# PowerConversionBoard.net
KiCad netlist of a schematic drawn in EAGLE
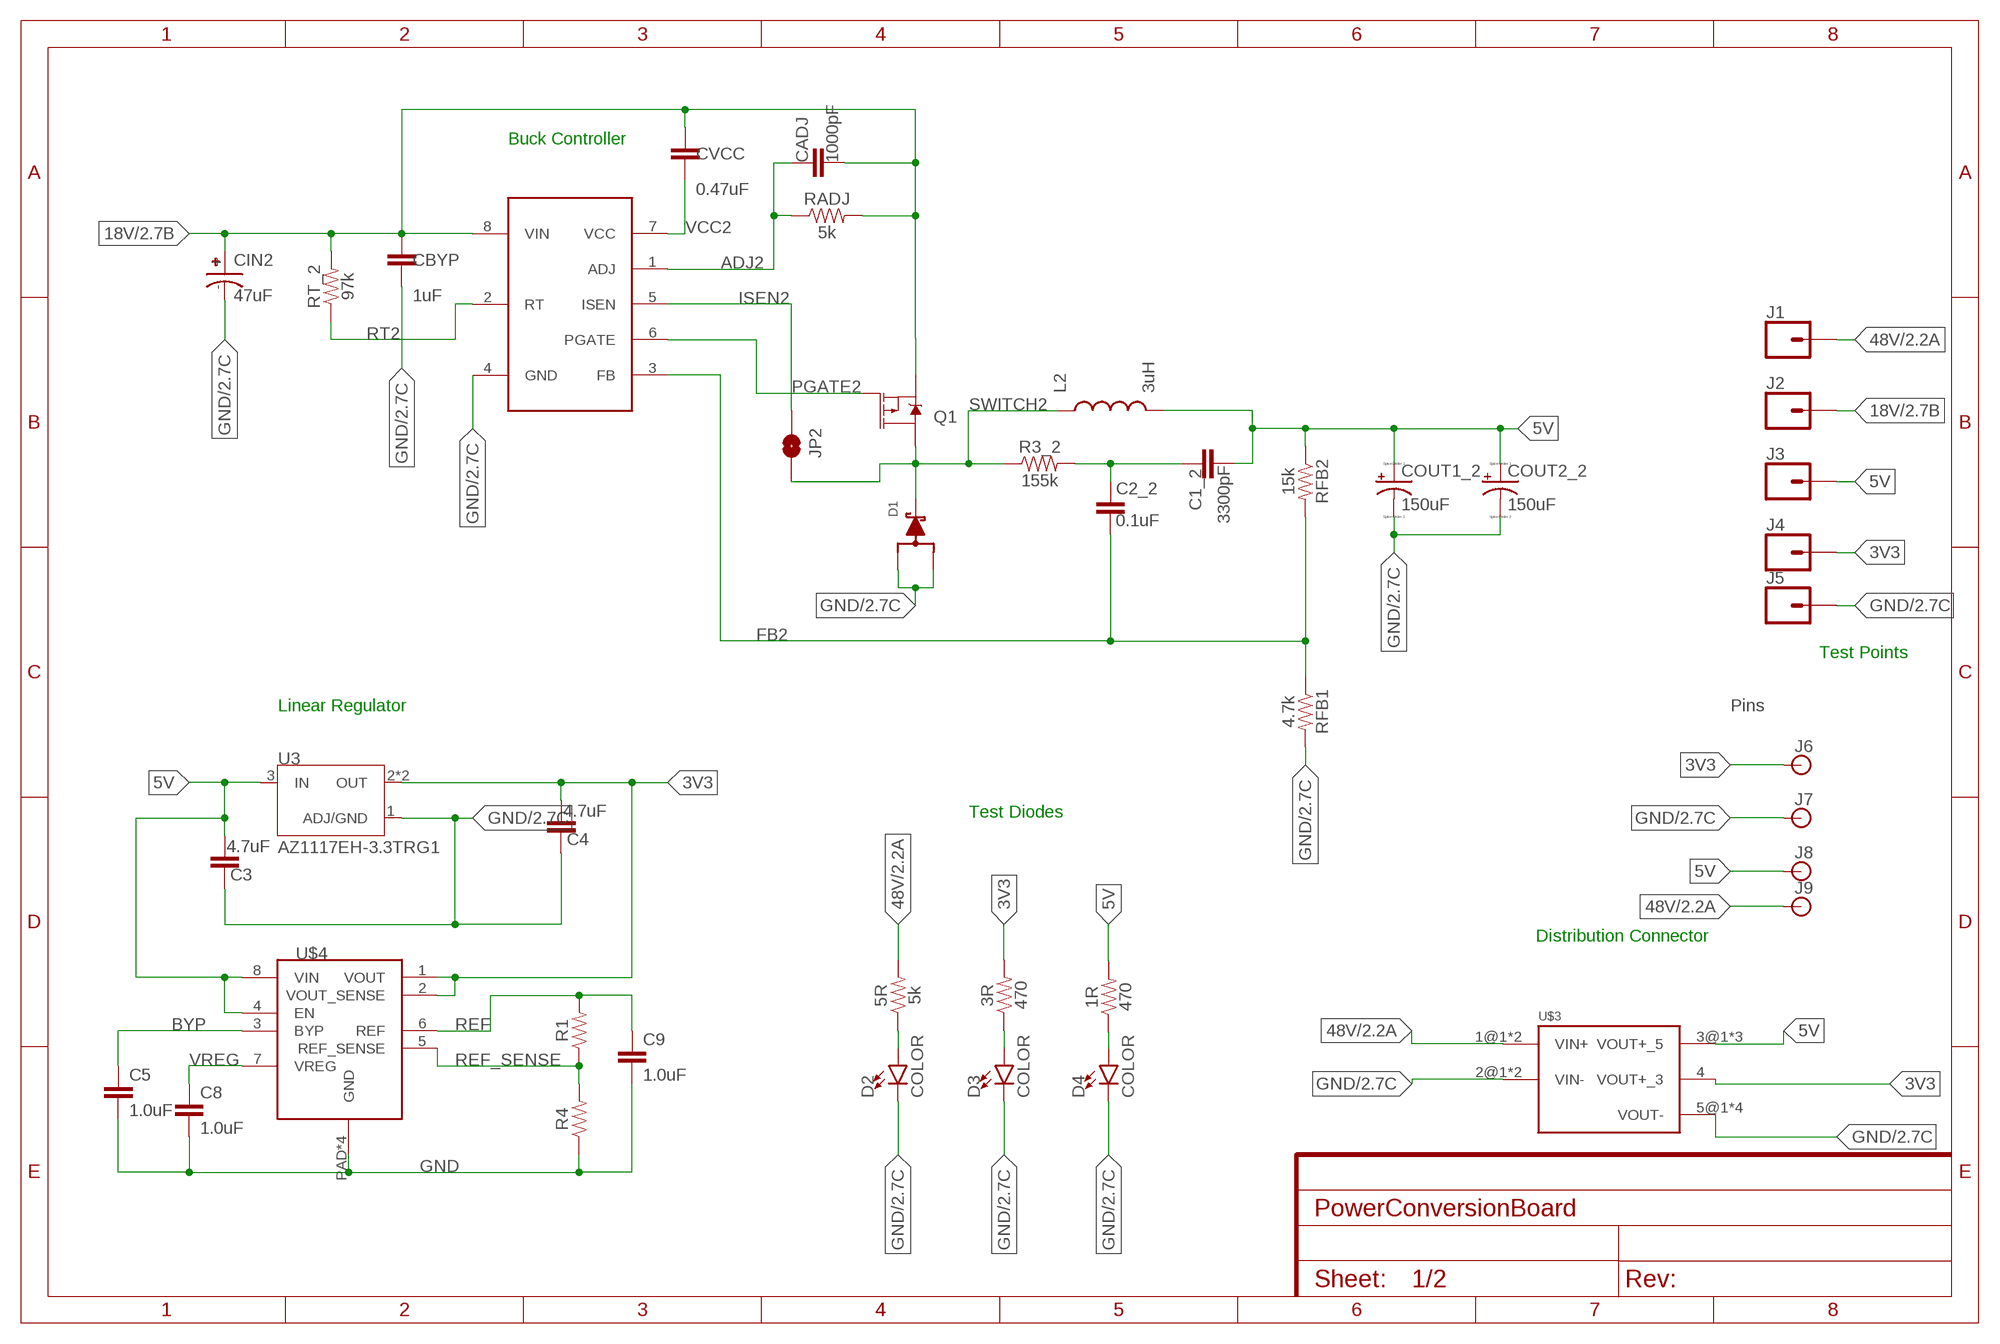
[diagram p0: schematic, sheet 1]
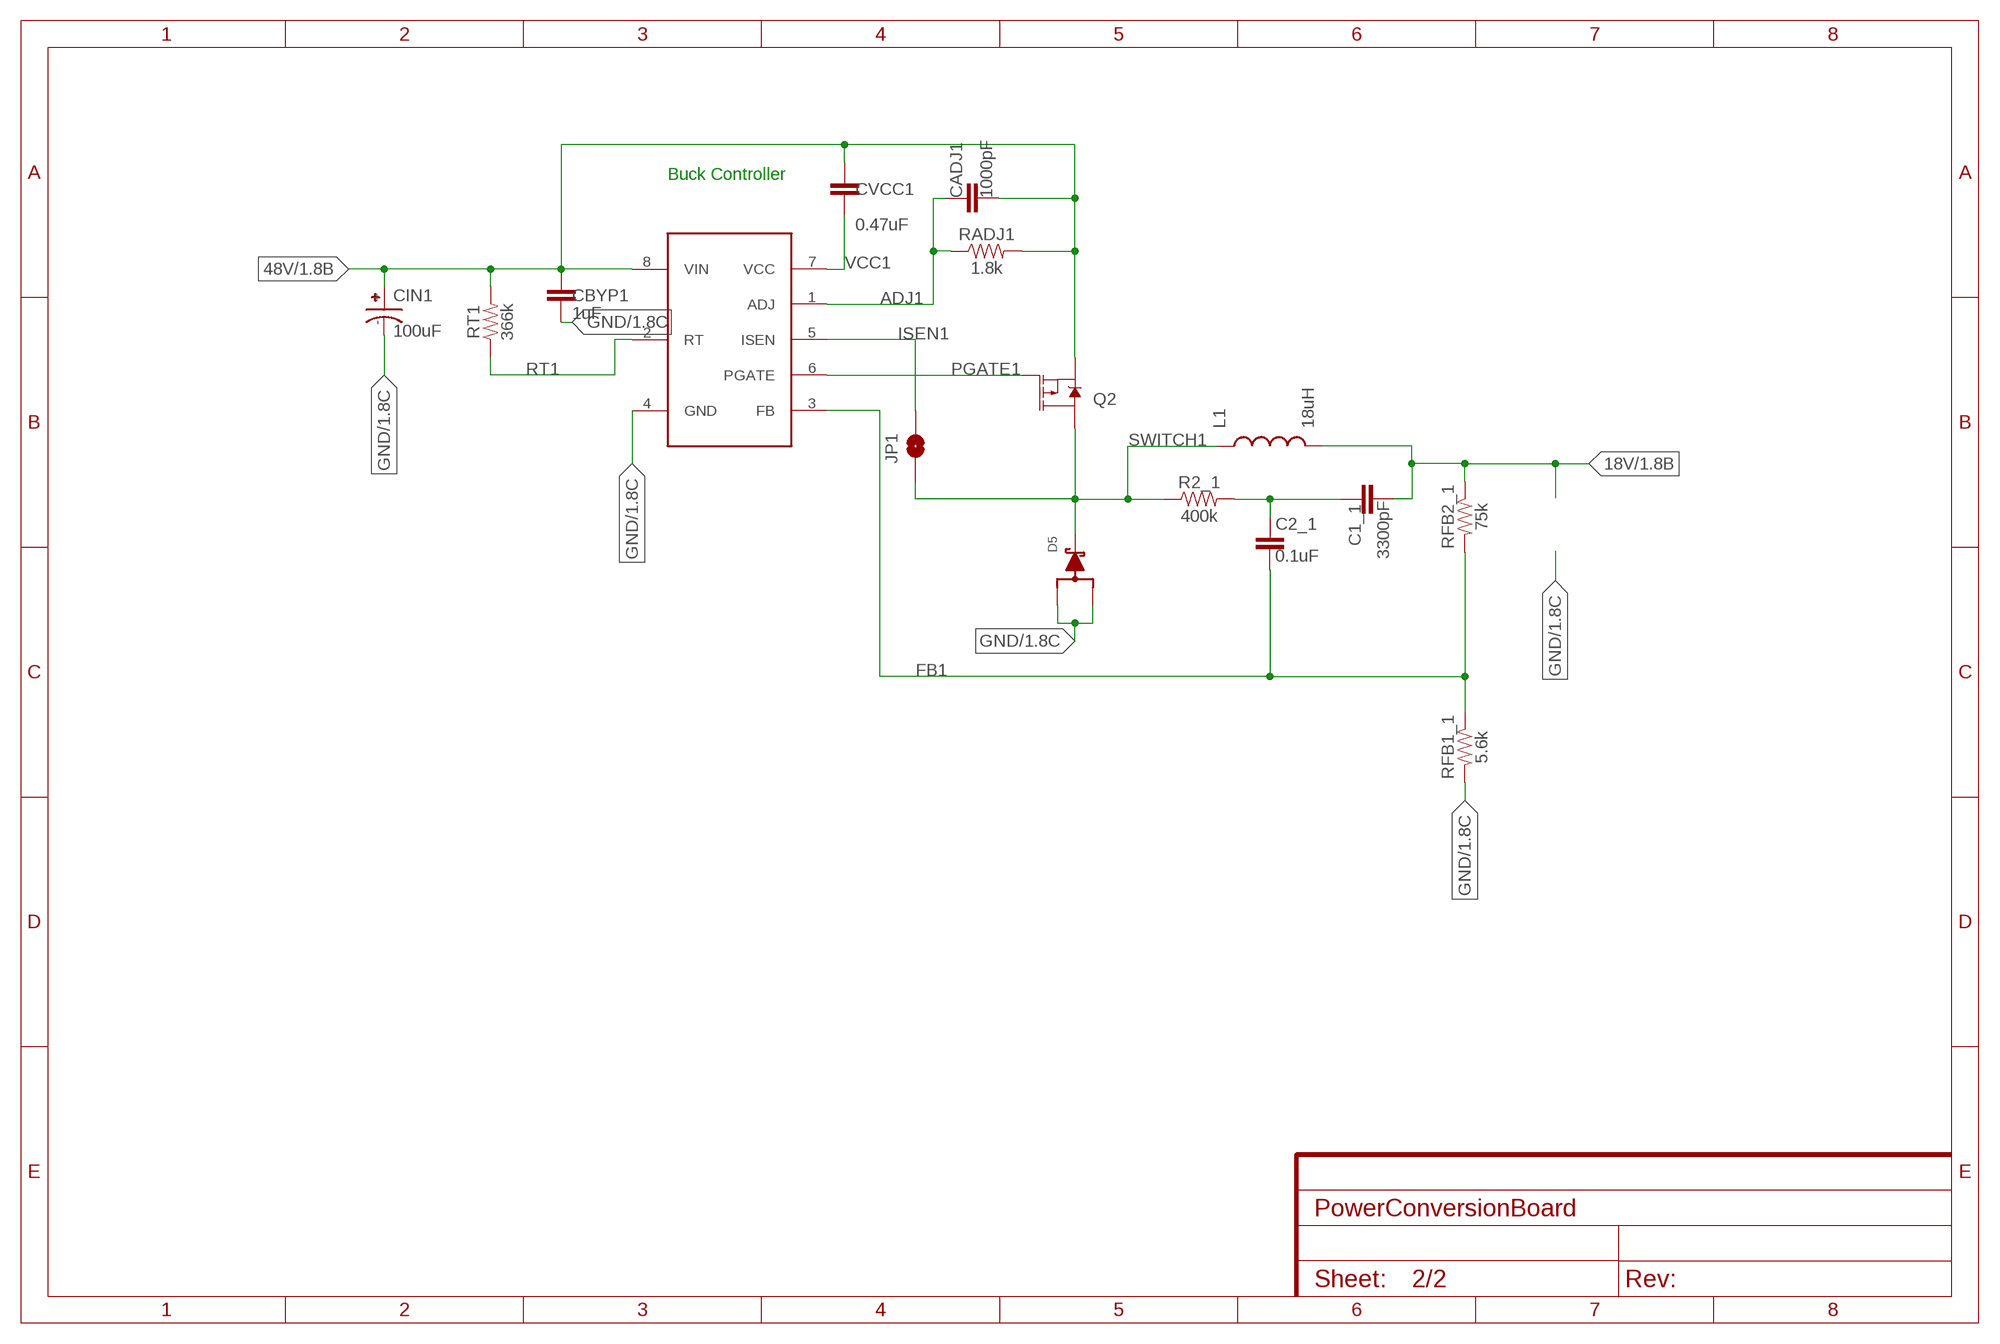
[diagram p1: schematic, sheet 2]

(export (version "E")
  (design (tool "Eeschema 10.0.6"))
  (components
    (comp (ref "1R")
      (value "470")
      (footprint "eagle-import:0603")
      (libsource (lib "eagle-import") (part "470OHM-0603-1/10W-1%"))
    )
    (comp (ref "3R")
      (value "470")
      (footprint "eagle-import:0603")
      (libsource (lib "eagle-import") (part "470OHM-0603-1/10W-1%"))
    )
    (comp (ref "5R")
      (value "5k")
      (footprint "eagle-import:0603")
      (libsource (lib "eagle-import") (part "470OHM-0603-1/10W-1%"))
    )
    (comp (ref "C1_2")
      (value "3300pF")
      (footprint "eagle-import:0603")
      (libsource (lib "eagle-import") (part "12PF-0603-50V-5%"))
    )
    (comp (ref "C2_2")
      (value "0.1uF")
      (footprint "eagle-import:0603")
      (libsource (lib "eagle-import") (part "12PF-0603-50V-5%"))
    )
    (comp (ref "C3")
      (value "4.7uF")
      (footprint "eagle-import:0603")
      (libsource (lib "eagle-import") (part "12PF-0603-50V-5%"))
    )
    (comp (ref "C4")
      (value "4.7uF")
      (footprint "eagle-import:0603")
      (libsource (lib "eagle-import") (part "12PF-0603-50V-5%"))
    )
    (comp (ref "C5")
      (value "1.0uF")
      (footprint "eagle-import:0603")
      (libsource (lib "eagle-import") (part "1.0UF-0603-16V-10%"))
    )
    (comp (ref "C8")
      (value "1.0uF")
      (footprint "eagle-import:0603")
      (libsource (lib "eagle-import") (part "1.0UF-0603-16V-10%"))
    )
    (comp (ref "C9")
      (value "1.0uF")
      (footprint "eagle-import:0603")
      (libsource (lib "eagle-import") (part "1.0UF-0603-16V-10%"))
    )
    (comp (ref "CADJ")
      (value "1000pF")
      (footprint "eagle-import:0603")
      (libsource (lib "eagle-import") (part "5.6PF-0603-50V-5%"))
    )
    (comp (ref "CBYP")
      (value "1uF")
      (footprint "eagle-import:0603")
      (libsource (lib "eagle-import") (part "3.3NF-0603-100V-10%"))
    )
    (comp (ref "CIN2")
      (value "47uF")
      (footprint "eagle-import:CAPAE1030X1050N")
      (fields
        (field (name "ARROW_PART_NUMBER") "UCM1H331MNL1GS")
        (field (name "MOUSER_PART_NUMBER") "647-UCM1H331MNL1GS")
      )
      (libsource (lib "eagle-import") (part "UCM1H331MNL1GS"))
    )
    (comp (ref "COUT1_2")
      (value "150uF")
      (footprint "eagle-import:CTAN(7.30_4.30MM)")
      (libsource (lib "eagle-import") (part "C-TANTALUM(10UF_150UF)"))
    )
    (comp (ref "COUT2_2")
      (value "150uF")
      (footprint "eagle-import:CTAN(7.30_4.30MM)")
      (libsource (lib "eagle-import") (part "C-TANTALUM(10UF_150UF)"))
    )
    (comp (ref "CVCC")
      (value "0.47uF")
      (footprint "eagle-import:0603")
      (libsource (lib "eagle-import") (part "5.6PF-0603-50V-5%"))
    )
    (comp (ref "D1")
      (value "SWITCHMODE_SCHOTTKY")
      (footprint "eagle-import:DPAK-3")
      (libsource (lib "eagle-import") (part "SWITCHMODE_SCHOTTKY"))
    )
    (comp (ref "D2")
      (value "COLOR")
      (footprint "eagle-import:0805")
      (libsource (lib "eagle-import") (part "LED-0805"))
    )
    (comp (ref "D3")
      (value "COLOR")
      (footprint "eagle-import:0805")
      (libsource (lib "eagle-import") (part "LED-0805"))
    )
    (comp (ref "D4")
      (value "COLOR")
      (footprint "eagle-import:0805")
      (libsource (lib "eagle-import") (part "LED-0805"))
    )
    (comp (ref "J1")
      (value "CONN_01")
      (footprint "eagle-import:1X01")
      (libsource (lib "eagle-import") (part "CONN_01"))
    )
    (comp (ref "J2")
      (value "CONN_01")
      (footprint "eagle-import:1X01")
      (libsource (lib "eagle-import") (part "CONN_01"))
    )
    (comp (ref "J3")
      (value "CONN_01")
      (footprint "eagle-import:1X01")
      (libsource (lib "eagle-import") (part "CONN_01"))
    )
    (comp (ref "J4")
      (value "CONN_01")
      (footprint "eagle-import:1X01")
      (libsource (lib "eagle-import") (part "CONN_01"))
    )
    (comp (ref "J5")
      (value "CONN_01")
      (footprint "eagle-import:1X01")
      (libsource (lib "eagle-import") (part "CONN_01"))
    )
    (comp (ref "J6")
      (value "BANANA_PTH")
      (footprint "eagle-import:BANANA_CONN_NO_THERM")
      (libsource (lib "eagle-import") (part "BANANA_PTH"))
    )
    (comp (ref "J7")
      (value "BANANA_PTH")
      (footprint "eagle-import:BANANA_CONN_NO_THERM")
      (libsource (lib "eagle-import") (part "BANANA_PTH"))
    )
    (comp (ref "J8")
      (value "BANANA_PTH")
      (footprint "eagle-import:BANANA_CONN_NO_THERM")
      (libsource (lib "eagle-import") (part "BANANA_PTH"))
    )
    (comp (ref "J9")
      (value "BANANA_PTH")
      (footprint "eagle-import:BANANA_CONN_NO_THERM")
      (libsource (lib "eagle-import") (part "BANANA_PTH"))
    )
    (comp (ref "JP2")
      (value "JUMPER-SMT_2_NO_SILK")
      (footprint "eagle-import:SMT-JUMPER_2_NO_SILK")
      (libsource (lib "eagle-import") (part "JUMPER-SMT_2_NO_SILK"))
    )
    (comp (ref "L2")
      (value "3uH")
      (footprint "eagle-import:HCMA1305")
      (libsource (lib "eagle-import") (part "HCMA1305"))
    )
    (comp (ref "Q1")
      (value "MOSFET_PCH-NDS8434")
      (footprint "eagle-import:SO08")
      (libsource (lib "eagle-import") (part "MOSFET_PCH-NDS8434"))
    )
    (comp (ref "R1")
      (value "RESISTOR0603")
      (footprint "eagle-import:0603")
      (libsource (lib "eagle-import") (part "RESISTOR0603"))
    )
    (comp (ref "R3_2")
      (value "155k")
      (footprint "eagle-import:0603")
      (libsource (lib "eagle-import") (part "RESISTOR0603"))
    )
    (comp (ref "R4")
      (value "RESISTOR0603")
      (footprint "eagle-import:0603")
      (libsource (lib "eagle-import") (part "RESISTOR0603"))
    )
    (comp (ref "RADJ")
      (value "5k")
      (footprint "eagle-import:0603")
      (libsource (lib "eagle-import") (part "RESISTOR0603"))
    )
    (comp (ref "RFB1")
      (value "4.7k")
      (footprint "eagle-import:0603")
      (libsource (lib "eagle-import") (part "RESISTOR0603"))
    )
    (comp (ref "RFB2")
      (value "15k")
      (footprint "eagle-import:0603")
      (libsource (lib "eagle-import") (part "RESISTOR0603"))
    )
    (comp (ref "RT_2")
      (value "97k")
      (footprint "eagle-import:0603")
      (libsource (lib "eagle-import") (part "82OHM-0603-1/10W-1%"))
    )
    (comp (ref "U$1")
      (value "LM5085")
      (footprint "eagle-import:LM5085")
      (libsource (lib "eagle-import") (part "LM5085"))
    )
    (comp (ref "U$3")
      (value "CON2DIST")
      (footprint "eagle-import:CON2DIST")
      (libsource (lib "eagle-import") (part "CON2DIST"))
    )
    (comp (ref "U$4")
      (value "ADP7159ARDZ-04-R7")
      (footprint "eagle-import:8-SOIC-EP")
      (libsource (lib "eagle-import") (part "ADP7159ARDZ-04-R7"))
    )
    (comp (ref "U3")
      (value "AZ1117EH-3.3TRG1")
      (footprint "eagle-import:SOT230P700X180-4N")
      (fields (field (name "MF") "Diodes Inc."))
      (libsource (lib "eagle-import") (part "AZ1117EH-3.3TRG1"))
    )
    (comp (ref "C1_1")
      (value "3300pF")
      (footprint "eagle-import:0603")
      (libsource (lib "eagle-import") (part "12PF-0603-50V-5%"))
    )
    (comp (ref "C2_1")
      (value "0.1uF")
      (footprint "eagle-import:0603")
      (libsource (lib "eagle-import") (part "12PF-0603-50V-5%"))
    )
    (comp (ref "CADJ1")
      (value "1000pF")
      (footprint "eagle-import:0603")
      (libsource (lib "eagle-import") (part "5.6PF-0603-50V-5%"))
    )
    (comp (ref "CBYP1")
      (value "1uF")
      (footprint "eagle-import:0603")
      (libsource (lib "eagle-import") (part "3.3NF-0603-100V-10%"))
    )
    (comp (ref "CIN1")
      (value "100uF")
      (footprint "eagle-import:CAPAE1030X1050N")
      (fields
        (field (name "ARROW_PART_NUMBER") "UCM1H331MNL1GS")
        (field (name "MOUSER_PART_NUMBER") "647-UCM1H331MNL1GS")
      )
      (libsource (lib "eagle-import") (part "UCM1H331MNL1GS"))
    )
    (comp (ref "CVCC1")
      (value "0.47uF")
      (footprint "eagle-import:0603")
      (libsource (lib "eagle-import") (part "5.6PF-0603-50V-5%"))
    )
    (comp (ref "D5")
      (value "SWITCHMODE_SCHOTTKY")
      (footprint "eagle-import:DPAK-3")
      (libsource (lib "eagle-import") (part "SWITCHMODE_SCHOTTKY"))
    )
    (comp (ref "JP1")
      (value "JUMPER-SMT_2_NO_SILK")
      (footprint "eagle-import:SMT-JUMPER_2_NO_SILK")
      (libsource (lib "eagle-import") (part "JUMPER-SMT_2_NO_SILK"))
    )
    (comp (ref "L1")
      (value "18uH")
      (footprint "eagle-import:HCMA1305")
      (libsource (lib "eagle-import") (part "HCMA1305"))
    )
    (comp (ref "Q2")
      (value "MOSFET_PCH-NDS8434")
      (footprint "eagle-import:SO08")
      (libsource (lib "eagle-import") (part "MOSFET_PCH-NDS8434"))
    )
    (comp (ref "R2_1")
      (value "400k")
      (footprint "eagle-import:0603")
      (libsource (lib "eagle-import") (part "RESISTOR0603"))
    )
    (comp (ref "RADJ1")
      (value "1.8k")
      (footprint "eagle-import:0603")
      (libsource (lib "eagle-import") (part "RESISTOR0603"))
    )
    (comp (ref "RFB1_1")
      (value "5.6k")
      (footprint "eagle-import:0603")
      (libsource (lib "eagle-import") (part "RESISTOR0603"))
    )
    (comp (ref "RFB2_1")
      (value "75k")
      (footprint "eagle-import:0603")
      (libsource (lib "eagle-import") (part "RESISTOR0603"))
    )
    (comp (ref "RT1")
      (value "366k")
      (footprint "eagle-import:0603")
      (libsource (lib "eagle-import") (part "82OHM-0603-1/10W-1%"))
    )
    (comp (ref "U$2")
      (value "LM5085")
      (footprint "eagle-import:LM5085")
      (libsource (lib "eagle-import") (part "LM5085"))
    )
  )
  (nets
    (net (code "1") (name "3V3") (class "Default")
      (node (ref "3R") (pin "2") (pinfunction "2_2") (pintype "passive"))
      (node (ref "C4") (pin "1") (pinfunction "1_1") (pintype "passive"))
      (node (ref "J4") (pin "1") (pinfunction "1_1") (pintype "passive"))
      (node (ref "J6") (pin "1") (pinfunction "1_1") (pintype "passive"))
      (node (ref "U$3") (pin "4") (pinfunction "VOUT+_3_4") (pintype "bidirectional"))
      (node (ref "U$4") (pin "1") (pinfunction "VOUT_1") (pintype "bidirectional"))
      (node (ref "U$4") (pin "2") (pinfunction "VOUT_SENSE_2") (pintype "bidirectional"))
      (node (ref "U3") (pin "2") (pinfunction "OUT_2") (pintype "output"))
      (node (ref "U3") (pin "4") (pinfunction "OUT_4") (pintype "output"))
    )
    (net (code "2") (name "5V") (class "Default")
      (node (ref "1R") (pin "2") (pinfunction "2_2") (pintype "passive"))
      (node (ref "C1_2") (pin "1") (pinfunction "1_1") (pintype "passive"))
      (node (ref "C3") (pin "1") (pinfunction "1_1") (pintype "passive"))
      (node (ref "COUT1_2") (pin "+") (pinfunction "+_+") (pintype "passive"))
      (node (ref "COUT2_2") (pin "+") (pinfunction "+_+") (pintype "passive"))
      (node (ref "J3") (pin "1") (pinfunction "1_1") (pintype "passive"))
      (node (ref "J8") (pin "1") (pinfunction "1_1") (pintype "passive"))
      (node (ref "L2") (pin "2") (pinfunction "2_2") (pintype "passive"))
      (node (ref "RFB2") (pin "1") (pinfunction "1_1") (pintype "passive"))
      (node (ref "U$3") (pin "3@1") (pinfunction "VOUT+_5_3@1") (pintype "bidirectional"))
      (node (ref "U$3") (pin "3@2") (pinfunction "VOUT+_5_3@2") (pintype "bidirectional"))
      (node (ref "U$3") (pin "3@3") (pinfunction "VOUT+_5_3@3") (pintype "bidirectional"))
      (node (ref "U$4") (pin "4") (pinfunction "EN_4") (pintype "bidirectional"))
      (node (ref "U$4") (pin "8") (pinfunction "VIN_8") (pintype "bidirectional"))
      (node (ref "U3") (pin "3") (pinfunction "IN_3") (pintype "input"))
    )
    (net (code "3") (name "18V") (class "Default")
      (node (ref "C1_1") (pin "1") (pinfunction "1_1") (pintype "passive"))
      (node (ref "CADJ") (pin "2") (pinfunction "2_2") (pintype "passive"))
      (node (ref "CBYP") (pin "1") (pinfunction "1_1") (pintype "passive"))
      (node (ref "CIN2") (pin "+") (pinfunction "+_+") (pintype "bidirectional"))
      (node (ref "CVCC") (pin "1") (pinfunction "1_1") (pintype "passive"))
      (node (ref "J2") (pin "1") (pinfunction "1_1") (pintype "passive"))
      (node (ref "L1") (pin "2") (pinfunction "2_2") (pintype "passive"))
      (node (ref "Q1") (pin "1") (pinfunction "S_1") (pintype "bidirectional"))
      (node (ref "Q1") (pin "2") (pinfunction "S_2") (pintype "bidirectional"))
      (node (ref "Q1") (pin "3") (pinfunction "S_3") (pintype "bidirectional"))
      (node (ref "RADJ") (pin "2") (pinfunction "2_2") (pintype "passive"))
      (node (ref "RFB2_1") (pin "1") (pinfunction "1_1") (pintype "passive"))
      (node (ref "RT_2") (pin "2") (pinfunction "2_2") (pintype "passive"))
      (node (ref "U$1") (pin "8") (pinfunction "VIN_8") (pintype "bidirectional"))
    )
    (net (code "4") (name "48V") (class "Default")
      (node (ref "5R") (pin "2") (pinfunction "2_2") (pintype "passive"))
      (node (ref "CADJ1") (pin "2") (pinfunction "2_2") (pintype "passive"))
      (node (ref "CBYP1") (pin "1") (pinfunction "1_1") (pintype "passive"))
      (node (ref "CIN1") (pin "+") (pinfunction "+_+") (pintype "bidirectional"))
      (node (ref "CVCC1") (pin "1") (pinfunction "1_1") (pintype "passive"))
      (node (ref "J1") (pin "1") (pinfunction "1_1") (pintype "passive"))
      (node (ref "J9") (pin "1") (pinfunction "1_1") (pintype "passive"))
      (node (ref "Q2") (pin "1") (pinfunction "S_1") (pintype "bidirectional"))
      (node (ref "Q2") (pin "2") (pinfunction "S_2") (pintype "bidirectional"))
      (node (ref "Q2") (pin "3") (pinfunction "S_3") (pintype "bidirectional"))
      (node (ref "RADJ1") (pin "2") (pinfunction "2_2") (pintype "passive"))
      (node (ref "RT1") (pin "2") (pinfunction "2_2") (pintype "passive"))
      (node (ref "U$2") (pin "8") (pinfunction "VIN_8") (pintype "bidirectional"))
      (node (ref "U$3") (pin "1@1") (pinfunction "VIN+_1@1") (pintype "bidirectional"))
      (node (ref "U$3") (pin "1@2") (pinfunction "VIN+_1@2") (pintype "bidirectional"))
    )
    (net (code "5") (name "ADJ1") (class "Default")
      (node (ref "CADJ1") (pin "1") (pinfunction "1_1") (pintype "passive"))
      (node (ref "RADJ1") (pin "1") (pinfunction "1_1") (pintype "passive"))
      (node (ref "U$2") (pin "1") (pinfunction "ADJ_1") (pintype "bidirectional"))
    )
    (net (code "6") (name "ADJ2") (class "Default")
      (node (ref "CADJ") (pin "1") (pinfunction "1_1") (pintype "passive"))
      (node (ref "RADJ") (pin "1") (pinfunction "1_1") (pintype "passive"))
      (node (ref "U$1") (pin "1") (pinfunction "ADJ_1") (pintype "bidirectional"))
    )
    (net (code "7") (name "BYP") (class "Default")
      (node (ref "C5") (pin "1") (pinfunction "1_1") (pintype "passive"))
      (node (ref "U$4") (pin "3") (pinfunction "BYP_3") (pintype "bidirectional"))
    )
    (net (code "8") (name "FB1") (class "Default")
      (node (ref "C2_1") (pin "2") (pinfunction "2_2") (pintype "passive"))
      (node (ref "RFB1_1") (pin "1") (pinfunction "1_1") (pintype "passive"))
      (node (ref "RFB2_1") (pin "2") (pinfunction "2_2") (pintype "passive"))
      (node (ref "U$2") (pin "3") (pinfunction "FB_3") (pintype "bidirectional"))
    )
    (net (code "9") (name "FB2") (class "Default")
      (node (ref "C2_2") (pin "2") (pinfunction "2_2") (pintype "passive"))
      (node (ref "RFB1") (pin "1") (pinfunction "1_1") (pintype "passive"))
      (node (ref "RFB2") (pin "2") (pinfunction "2_2") (pintype "passive"))
      (node (ref "U$1") (pin "3") (pinfunction "FB_3") (pintype "bidirectional"))
    )
    (net (code "10") (name "GND") (class "Default")
      (node (ref "C3") (pin "2") (pinfunction "2_2") (pintype "passive"))
      (node (ref "C4") (pin "2") (pinfunction "2_2") (pintype "passive"))
      (node (ref "C5") (pin "2") (pinfunction "2_2") (pintype "passive"))
      (node (ref "C8") (pin "2") (pinfunction "2_2") (pintype "passive"))
      (node (ref "C9") (pin "2") (pinfunction "2_2") (pintype "passive"))
      (node (ref "CBYP") (pin "2") (pinfunction "2_2") (pintype "passive"))
      (node (ref "CBYP1") (pin "2") (pinfunction "2_2") (pintype "passive"))
      (node (ref "CIN1") (pin "-") (pinfunction "-_-") (pintype "bidirectional"))
      (node (ref "CIN2") (pin "-") (pinfunction "-_-") (pintype "bidirectional"))
      (node (ref "COUT1_2") (pin "-") (pinfunction "-_-") (pintype "passive"))
      (node (ref "COUT2_2") (pin "-") (pinfunction "-_-") (pintype "passive"))
      (node (ref "D1") (pin "1") (pinfunction "A_1") (pintype "bidirectional"))
      (node (ref "D1") (pin "3") (pinfunction "A_3") (pintype "bidirectional"))
      (node (ref "D2") (pin "C") (pinfunction "C_C") (pintype "passive"))
      (node (ref "D3") (pin "C") (pinfunction "C_C") (pintype "passive"))
      (node (ref "D4") (pin "C") (pinfunction "C_C") (pintype "passive"))
      (node (ref "D5") (pin "1") (pinfunction "A_1") (pintype "bidirectional"))
      (node (ref "D5") (pin "3") (pinfunction "A_3") (pintype "bidirectional"))
      (node (ref "J5") (pin "1") (pinfunction "1_1") (pintype "passive"))
      (node (ref "J7") (pin "1") (pinfunction "1_1") (pintype "passive"))
      (node (ref "R4") (pin "1") (pinfunction "1_1") (pintype "passive"))
      (node (ref "RFB1") (pin "2") (pinfunction "2_2") (pintype "passive"))
      (node (ref "RFB1_1") (pin "2") (pinfunction "2_2") (pintype "passive"))
      (node (ref "U$1") (pin "4") (pinfunction "GND_4") (pintype "bidirectional"))
      (node (ref "U$2") (pin "4") (pinfunction "GND_4") (pintype "bidirectional"))
      (node (ref "U$3") (pin "2@1") (pinfunction "VIN-_2@1") (pintype "bidirectional"))
      (node (ref "U$3") (pin "2@2") (pinfunction "VIN-_2@2") (pintype "bidirectional"))
      (node (ref "U$3") (pin "5@1") (pinfunction "VOUT-_5@1") (pintype "bidirectional"))
      (node (ref "U$3") (pin "5@2") (pinfunction "VOUT-_5@2") (pintype "bidirectional"))
      (node (ref "U$3") (pin "5@3") (pinfunction "VOUT-_5@3") (pintype "bidirectional"))
      (node (ref "U$3") (pin "5@4") (pinfunction "VOUT-_5@4") (pintype "bidirectional"))
      (node (ref "U$4") (pin "PAD") (pinfunction "GND_PAD") (pintype "bidirectional"))
      (node (ref "U$4") (pin "PAD_BOT") (pinfunction "GND_PAD_BOT") (pintype "bidirectional"))
      (node (ref "U$4") (pin "PAD_VIA1") (pinfunction "GND_PAD_VIA1") (pintype "bidirectional"))
      (node (ref "U$4") (pin "PAD_VIA2") (pinfunction "GND_PAD_VIA2") (pintype "bidirectional"))
      (node (ref "U3") (pin "1") (pinfunction "ADJ/GND_1") (pintype "power_in"))
    )
    (net (code "11") (name "ISEN1") (class "Default")
      (node (ref "JP1") (pin "2") (pinfunction "2_2") (pintype "passive"))
      (node (ref "U$2") (pin "5") (pinfunction "ISEN_5") (pintype "bidirectional"))
    )
    (net (code "12") (name "ISEN2") (class "Default")
      (node (ref "JP2") (pin "1") (pinfunction "1_1") (pintype "passive"))
      (node (ref "U$1") (pin "5") (pinfunction "ISEN_5") (pintype "bidirectional"))
    )
    (net (code "13") (name "Net-(1R-Pad1)") (class "Default")
      (node (ref "1R") (pin "1") (pinfunction "1_1") (pintype "passive"))
      (node (ref "D4") (pin "A") (pinfunction "A_A") (pintype "passive"))
    )
    (net (code "14") (name "Net-(3R-Pad1)") (class "Default")
      (node (ref "3R") (pin "1") (pinfunction "1_1") (pintype "passive"))
      (node (ref "D3") (pin "A") (pinfunction "A_A") (pintype "passive"))
    )
    (net (code "15") (name "Net-(5R-Pad1)") (class "Default")
      (node (ref "5R") (pin "1") (pinfunction "1_1") (pintype "passive"))
      (node (ref "D2") (pin "A") (pinfunction "A_A") (pintype "passive"))
    )
    (net (code "16") (name "Net-(C1_1-Pad2)") (class "Default")
      (node (ref "C1_1") (pin "2") (pinfunction "2_2") (pintype "passive"))
      (node (ref "C2_1") (pin "1") (pinfunction "1_1") (pintype "passive"))
      (node (ref "R2_1") (pin "2") (pinfunction "2_2") (pintype "passive"))
    )
    (net (code "17") (name "Net-(C1_2-Pad2)") (class "Default")
      (node (ref "C1_2") (pin "2") (pinfunction "2_2") (pintype "passive"))
      (node (ref "C2_2") (pin "1") (pinfunction "1_1") (pintype "passive"))
      (node (ref "R3_2") (pin "2") (pinfunction "2_2") (pintype "passive"))
    )
    (net (code "18") (name "PGATE1") (class "Default")
      (node (ref "Q2") (pin "4") (pinfunction "G_4") (pintype "bidirectional"))
      (node (ref "U$2") (pin "6") (pinfunction "PGATE_6") (pintype "bidirectional"))
    )
    (net (code "19") (name "PGATE2") (class "Default")
      (node (ref "Q1") (pin "4") (pinfunction "G_4") (pintype "bidirectional"))
      (node (ref "U$1") (pin "6") (pinfunction "PGATE_6") (pintype "bidirectional"))
    )
    (net (code "20") (name "REF") (class "Default")
      (node (ref "C9") (pin "1") (pinfunction "1_1") (pintype "passive"))
      (node (ref "R1") (pin "2") (pinfunction "2_2") (pintype "passive"))
      (node (ref "U$4") (pin "6") (pinfunction "REF_6") (pintype "bidirectional"))
    )
    (net (code "21") (name "REF_SENSE") (class "Default")
      (node (ref "R1") (pin "1") (pinfunction "1_1") (pintype "passive"))
      (node (ref "R4") (pin "2") (pinfunction "2_2") (pintype "passive"))
      (node (ref "U$4") (pin "5") (pinfunction "REF_SENSE_5") (pintype "bidirectional"))
    )
    (net (code "22") (name "RT1") (class "Default")
      (node (ref "RT1") (pin "1") (pinfunction "1_1") (pintype "passive"))
      (node (ref "U$2") (pin "2") (pinfunction "RT_2") (pintype "bidirectional"))
    )
    (net (code "23") (name "RT2") (class "Default")
      (node (ref "RT_2") (pin "1") (pinfunction "1_1") (pintype "passive"))
      (node (ref "U$1") (pin "2") (pinfunction "RT_2") (pintype "bidirectional"))
    )
    (net (code "24") (name "SWITCH1") (class "Default")
      (node (ref "D5") (pin "4") (pinfunction "C_4") (pintype "bidirectional"))
      (node (ref "JP1") (pin "1") (pinfunction "1_1") (pintype "passive"))
      (node (ref "L1") (pin "1") (pinfunction "1_1") (pintype "passive"))
      (node (ref "Q2") (pin "5") (pinfunction "D_5") (pintype "bidirectional"))
      (node (ref "Q2") (pin "6") (pinfunction "D_6") (pintype "bidirectional"))
      (node (ref "Q2") (pin "7") (pinfunction "D_7") (pintype "bidirectional"))
      (node (ref "Q2") (pin "8") (pinfunction "D_8") (pintype "bidirectional"))
      (node (ref "R2_1") (pin "1") (pinfunction "1_1") (pintype "passive"))
    )
    (net (code "25") (name "SWITCH2") (class "Default")
      (node (ref "D1") (pin "4") (pinfunction "C_4") (pintype "bidirectional"))
      (node (ref "JP2") (pin "2") (pinfunction "2_2") (pintype "passive"))
      (node (ref "L2") (pin "1") (pinfunction "1_1") (pintype "passive"))
      (node (ref "Q1") (pin "5") (pinfunction "D_5") (pintype "bidirectional"))
      (node (ref "Q1") (pin "6") (pinfunction "D_6") (pintype "bidirectional"))
      (node (ref "Q1") (pin "7") (pinfunction "D_7") (pintype "bidirectional"))
      (node (ref "Q1") (pin "8") (pinfunction "D_8") (pintype "bidirectional"))
      (node (ref "R3_2") (pin "1") (pinfunction "1_1") (pintype "passive"))
    )
    (net (code "26") (name "VCC1") (class "Default")
      (node (ref "CVCC1") (pin "2") (pinfunction "2_2") (pintype "passive"))
      (node (ref "U$2") (pin "7") (pinfunction "VCC_7") (pintype "bidirectional"))
    )
    (net (code "27") (name "VCC2") (class "Default")
      (node (ref "CVCC") (pin "2") (pinfunction "2_2") (pintype "passive"))
      (node (ref "U$1") (pin "7") (pinfunction "VCC_7") (pintype "bidirectional"))
    )
    (net (code "28") (name "VREG") (class "Default")
      (node (ref "C8") (pin "1") (pinfunction "1_1") (pintype "passive"))
      (node (ref "U$4") (pin "7") (pinfunction "VREG_7") (pintype "bidirectional"))
    )
  )
)
